# LogiGSM.net
KiCad netlist of a schematic drawn in EAGLE
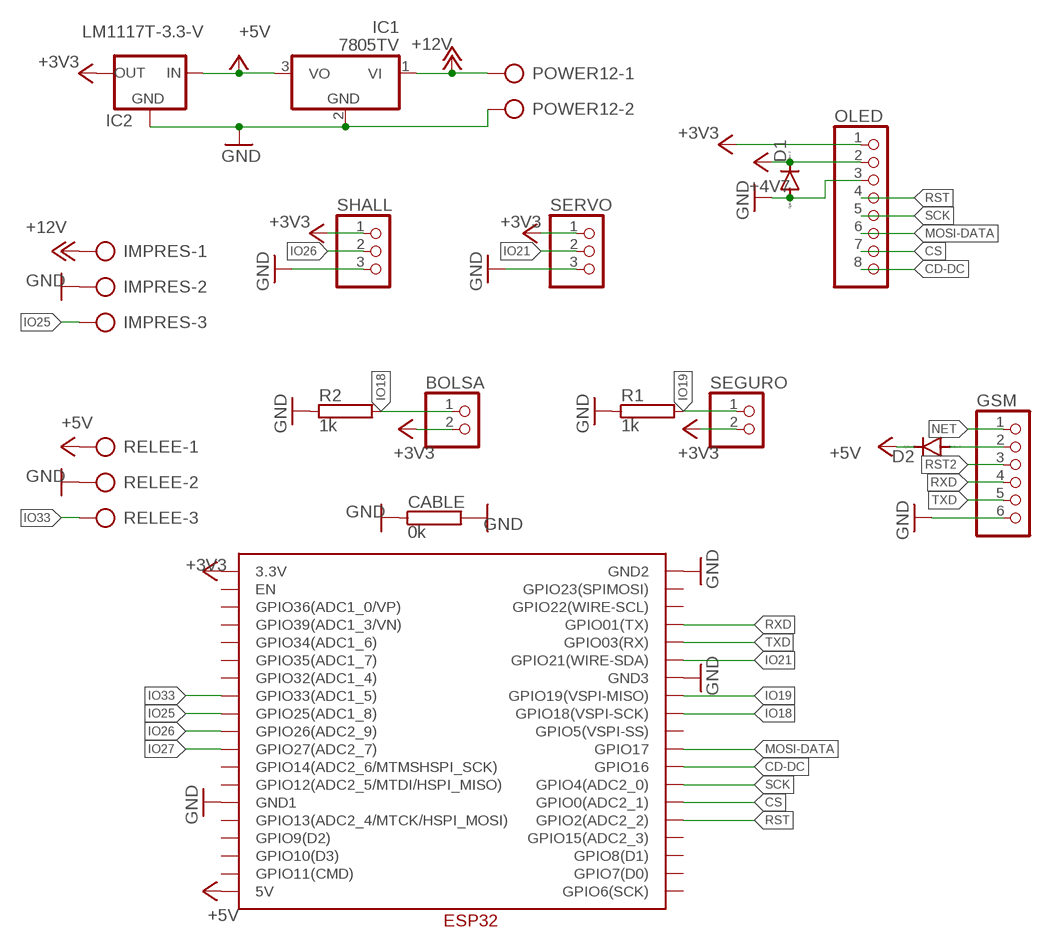
[diagram p0: schematic, sheet 1]

(export (version "E")
  (design (tool "Eeschema 10.0.6"))
  (components
    (comp (ref "BOLSA")
      (value "PINHD-1X2")
      (footprint "eagle-import:1X02")
      (libsource (lib "eagle-import") (part "PINHD-1X2"))
    )
    (comp (ref "CABLE")
      (value "0k")
      (footprint "eagle-import:RS1_2")
      (fields (field (name "MF") "OHMITE") (field (name "MPN") "RRS1K0E"))
      (libsource (lib "eagle-import") (part "RRS1/2"))
    )
    (comp (ref "D1")
      (value "DIODE-SOD81")
      (footprint "eagle-import:SOD81")
      (libsource (lib "eagle-import") (part "DIODE-SOD81"))
    )
    (comp (ref "D2")
      (value "DIODE-SOD81")
      (footprint "eagle-import:SOD81")
      (libsource (lib "eagle-import") (part "DIODE-SOD81"))
    )
    (comp (ref "GSM")
      (value "PINHD-1X6")
      (footprint "eagle-import:1X06")
      (libsource (lib "eagle-import") (part "PINHD-1X6"))
    )
    (comp (ref "IC1")
      (value "7805TV")
      (footprint "eagle-import:TO220V")
      (libsource (lib "eagle-import") (part "78TV05"))
    )
    (comp (ref "IC2")
      (value "LM1117T-3.3-V")
      (footprint "eagle-import:TO220V")
      (libsource (lib "eagle-import") (part "LM1117T--V3.3"))
    )
    (comp (ref "IMPRES")
      (value "AK500/3")
      (footprint "eagle-import:AK500_3")
      (libsource (lib "eagle-import") (part "AK500/3"))
    )
    (comp (ref "OLED")
      (value "PINHD-1X8")
      (footprint "eagle-import:1X08")
      (libsource (lib "eagle-import") (part "PINHD-1X8"))
    )
    (comp (ref "POWER12")
      (value "AK500/2")
      (footprint "eagle-import:AK500_2")
      (libsource (lib "eagle-import") (part "AK500/2"))
    )
    (comp (ref "R1")
      (value "1k")
      (footprint "eagle-import:RS1_8")
      (libsource (lib "eagle-import") (part "resistor-powerV2_RRS1/8"))
    )
    (comp (ref "R2")
      (value "1k")
      (footprint "eagle-import:RS1_8")
      (libsource (lib "eagle-import") (part "resistor-powerV2_RRS1/8"))
    )
    (comp (ref "RELEE")
      (value "AK500/3")
      (footprint "eagle-import:AK500_3")
      (libsource (lib "eagle-import") (part "AK500/3"))
    )
    (comp (ref "SEGURO")
      (value "PINHD-1X2")
      (footprint "eagle-import:1X02")
      (libsource (lib "eagle-import") (part "PINHD-1X2"))
    )
    (comp (ref "SERVO")
      (value "PINHD-1X3")
      (footprint "eagle-import:1X03")
      (libsource (lib "eagle-import") (part "PINHD-1X3"))
    )
    (comp (ref "SHALL")
      (value "PINHD-1X3")
      (footprint "eagle-import:1X03")
      (libsource (lib "eagle-import") (part "PINHD-1X3"))
    )
    (comp (ref "U$1")
      (value "ESP32WESP32W")
      (footprint "eagle-import:ESP32W")
      (libsource (lib "eagle-import") (part "ESP32WESP32W"))
    )
  )
  (nets
    (net (code "1") (name "+3V3") (class "Default")
      (node (ref "BOLSA") (pin "2") (pinfunction "2_2") (pintype "passive"))
      (node (ref "IC2") (pin "2") (pinfunction "OUT_2") (pintype "passive"))
      (node (ref "OLED") (pin "1") (pinfunction "1_1") (pintype "passive"))
      (node (ref "SEGURO") (pin "2") (pinfunction "2_2") (pintype "passive"))
      (node (ref "SERVO") (pin "1") (pinfunction "1_1") (pintype "passive"))
      (node (ref "SHALL") (pin "1") (pinfunction "1_1") (pintype "passive"))
      (node (ref "U$1") (pin "3.3V") (pinfunction "3.3V_3.3V") (pintype "bidirectional"))
    )
    (net (code "2") (name "+4V7") (class "Default")
      (node (ref "D1") (pin "C") (pinfunction "C_C") (pintype "passive"))
      (node (ref "D2") (pin "C") (pinfunction "C_C") (pintype "passive"))
      (node (ref "IC1") (pin "3") (pinfunction "VO_3") (pintype "passive"))
      (node (ref "IC2") (pin "3") (pinfunction "IN_3") (pintype "input"))
      (node (ref "OLED") (pin "2") (pinfunction "2_2") (pintype "passive"))
      (node (ref "RELEE") (pin "1") (pinfunction "KL_1") (pintype "passive"))
      (node (ref "U$1") (pin "5V") (pinfunction "5V_5V") (pintype "bidirectional"))
    )
    (net (code "3") (name "+12V") (class "Default")
      (node (ref "IC1") (pin "1") (pinfunction "VI_1") (pintype "input"))
      (node (ref "IMPRES") (pin "1") (pinfunction "KL_1") (pintype "passive"))
      (node (ref "POWER12") (pin "1") (pinfunction "KL_1") (pintype "passive"))
    )
    (net (code "4") (name "CD-DC") (class "Default")
      (node (ref "OLED") (pin "8") (pinfunction "8_8") (pintype "passive"))
      (node (ref "U$1") (pin "GPIO16") (pinfunction "GPIO16_GPIO16") (pintype "bidirectional"))
    )
    (net (code "5") (name "CS") (class "Default")
      (node (ref "OLED") (pin "7") (pinfunction "7_7") (pintype "passive"))
      (node (ref "U$1") (pin "GPIO0") (pinfunction "GPIO0(ADC2_1)_GPIO0") (pintype "bidirectional"))
    )
    (net (code "6") (name "GND") (class "Default")
      (node (ref "CABLE") (pin "1") (pinfunction "1_1") (pintype "passive"))
      (node (ref "CABLE") (pin "2") (pinfunction "2_2") (pintype "passive"))
      (node (ref "D1") (pin "A") (pinfunction "A_A") (pintype "passive"))
      (node (ref "GSM") (pin "6") (pinfunction "6_6") (pintype "passive"))
      (node (ref "IC1") (pin "2") (pinfunction "GND_2") (pintype "passive"))
      (node (ref "IC2") (pin "1") (pinfunction "GND_1") (pintype "input"))
      (node (ref "IMPRES") (pin "2") (pinfunction "KL_2") (pintype "passive"))
      (node (ref "OLED") (pin "3") (pinfunction "3_3") (pintype "passive"))
      (node (ref "POWER12") (pin "2") (pinfunction "KL_2") (pintype "passive"))
      (node (ref "R1") (pin "1") (pinfunction "1_1") (pintype "passive"))
      (node (ref "R2") (pin "1") (pinfunction "1_1") (pintype "passive"))
      (node (ref "RELEE") (pin "2") (pinfunction "KL_2") (pintype "passive"))
      (node (ref "SERVO") (pin "3") (pinfunction "3_3") (pintype "passive"))
      (node (ref "SHALL") (pin "3") (pinfunction "3_3") (pintype "passive"))
      (node (ref "U$1") (pin "GND1") (pinfunction "GND1_GND1") (pintype "bidirectional"))
      (node (ref "U$1") (pin "GND2") (pinfunction "GND2_GND2") (pintype "bidirectional"))
      (node (ref "U$1") (pin "GND3") (pinfunction "GND3_GND3") (pintype "bidirectional"))
    )
    (net (code "7") (name "IO18") (class "Default")
      (node (ref "BOLSA") (pin "1") (pinfunction "1_1") (pintype "passive"))
      (node (ref "R2") (pin "2") (pinfunction "2_2") (pintype "passive"))
      (node (ref "U$1") (pin "GPIO18") (pinfunction "GPIO18(VSPI-SCK)_GPIO18") (pintype "bidirectional"))
    )
    (net (code "8") (name "IO19") (class "Default")
      (node (ref "R1") (pin "2") (pinfunction "2_2") (pintype "passive"))
      (node (ref "SEGURO") (pin "1") (pinfunction "1_1") (pintype "passive"))
      (node (ref "U$1") (pin "GPIO19") (pinfunction "GPIO19(VSPI-MISO)_GPIO19") (pintype "bidirectional"))
    )
    (net (code "9") (name "IO21") (class "Default")
      (node (ref "SERVO") (pin "2") (pinfunction "2_2") (pintype "passive"))
      (node (ref "U$1") (pin "GPIO21") (pinfunction "GPIO21(WIRE-SDA)_GPIO21") (pintype "bidirectional"))
    )
    (net (code "10") (name "IO25") (class "Default")
      (node (ref "IMPRES") (pin "3") (pinfunction "KL_3") (pintype "passive"))
      (node (ref "U$1") (pin "GPIO25") (pinfunction "GPIO25(ADC1_8)_GPIO25") (pintype "bidirectional"))
    )
    (net (code "11") (name "IO26") (class "Default")
      (node (ref "SHALL") (pin "2") (pinfunction "2_2") (pintype "passive"))
      (node (ref "U$1") (pin "GPIO26") (pinfunction "GPIO26(ADC2_9)_GPIO26") (pintype "bidirectional"))
    )
    (net (code "12") (name "IO27") (class "Default")
      (node (ref "U$1") (pin "GPIO27") (pinfunction "GPIO27(ADC2_7)_GPIO27") (pintype "bidirectional"))
    )
    (net (code "13") (name "IO33") (class "Default")
      (node (ref "RELEE") (pin "3") (pinfunction "KL_3") (pintype "passive"))
      (node (ref "U$1") (pin "GPIO33") (pinfunction "GPIO33(ADC1_5)_GPIO33") (pintype "bidirectional"))
    )
    (net (code "14") (name "MOSI-DATA") (class "Default")
      (node (ref "OLED") (pin "6") (pinfunction "6_6") (pintype "passive"))
      (node (ref "U$1") (pin "GPIO17") (pinfunction "GPIO17_GPIO17") (pintype "bidirectional"))
    )
    (net (code "15") (name "NET") (class "Default")
      (node (ref "GSM") (pin "1") (pinfunction "1_1") (pintype "passive"))
    )
    (net (code "16") (name "Net-(D2-PadA)") (class "Default")
      (node (ref "D2") (pin "A") (pinfunction "A_A") (pintype "passive"))
      (node (ref "GSM") (pin "2") (pinfunction "2_2") (pintype "passive"))
    )
    (net (code "17") (name "RST") (class "Default")
      (node (ref "OLED") (pin "4") (pinfunction "4_4") (pintype "passive"))
      (node (ref "U$1") (pin "GPIO2") (pinfunction "GPIO2(ADC2_2)_GPIO2") (pintype "bidirectional"))
    )
    (net (code "18") (name "RST2") (class "Default")
      (node (ref "GSM") (pin "3") (pinfunction "3_3") (pintype "passive"))
    )
    (net (code "19") (name "RXD") (class "Default")
      (node (ref "GSM") (pin "4") (pinfunction "4_4") (pintype "passive"))
      (node (ref "U$1") (pin "TX") (pinfunction "GPIO01(TX)_TX") (pintype "bidirectional"))
    )
    (net (code "20") (name "SCK") (class "Default")
      (node (ref "OLED") (pin "5") (pinfunction "5_5") (pintype "passive"))
      (node (ref "U$1") (pin "GPIO4") (pinfunction "GPIO4(ADC2_0)_GPIO4") (pintype "bidirectional"))
    )
    (net (code "21") (name "TXD") (class "Default")
      (node (ref "GSM") (pin "5") (pinfunction "5_5") (pintype "passive"))
      (node (ref "U$1") (pin "RX") (pinfunction "GPIO03(RX)_RX") (pintype "bidirectional"))
    )
    (net (code "22") (name "unconnected-(U$1-GPIO5(VSPI-SS)-PadGPIO5)") (class "Default")
      (node (ref "U$1") (pin "GPIO5") (pinfunction "GPIO5(VSPI-SS)_GPIO5") (pintype "bidirectional"))
    )
    (net (code "23") (name "unconnected-(U$1-GPIO6(SCK)-PadCLK)") (class "Default")
      (node (ref "U$1") (pin "CLK") (pinfunction "GPIO6(SCK)_CLK") (pintype "bidirectional"))
    )
    (net (code "24") (name "unconnected-(U$1-GPIO7(D0)-PadSDO)") (class "Default")
      (node (ref "U$1") (pin "SDO") (pinfunction "GPIO7(D0)_SDO") (pintype "bidirectional"))
    )
    (net (code "25") (name "unconnected-(U$1-GPIO8(D1)-PadSDI)") (class "Default")
      (node (ref "U$1") (pin "SDI") (pinfunction "GPIO8(D1)_SDI") (pintype "bidirectional"))
    )
    (net (code "26") (name "unconnected-(U$1-GPIO9(D2)-PadD2)") (class "Default")
      (node (ref "U$1") (pin "D2") (pinfunction "GPIO9(D2)_D2") (pintype "bidirectional"))
    )
    (net (code "27") (name "unconnected-(U$1-GPIO10(D3)-PadD3)") (class "Default")
      (node (ref "U$1") (pin "D3") (pinfunction "GPIO10(D3)_D3") (pintype "bidirectional"))
    )
    (net (code "28") (name "unconnected-(U$1-GPIO11(CMD)-PadCMD)") (class "Default")
      (node (ref "U$1") (pin "CMD") (pinfunction "GPIO11(CMD)_CMD") (pintype "bidirectional"))
    )
    (net (code "29") (name "unconnected-(U$1-GPIO12(ADC2_5{slash}MTDI{slash}HSPI_MISO)-PadGPIO12)") (class "Default")
      (node (ref "U$1") (pin "GPIO12") (pinfunction "GPIO12(ADC2_5/MTDI/HSPI_MISO)_GPIO12") (pintype "bidirectional"))
    )
    (net (code "30") (name "unconnected-(U$1-GPIO13(ADC2_4{slash}MTCK{slash}HSPI_MOSI)-PadGPIO13)") (class "Default")
      (node (ref "U$1") (pin "GPIO13") (pinfunction "GPIO13(ADC2_4/MTCK/HSPI_MOSI)_GPIO13") (pintype "bidirectional"))
    )
    (net (code "31") (name "unconnected-(U$1-GPIO14(ADC2_6{slash}MTMSHSPI_SCK)-PadGPIO14)") (class "Default")
      (node (ref "U$1") (pin "GPIO14") (pinfunction "GPIO14(ADC2_6/MTMSHSPI_SCK)_GPIO14") (pintype "bidirectional"))
    )
    (net (code "32") (name "unconnected-(U$1-GPIO15(ADC2_3)-PadGPIO15)") (class "Default")
      (node (ref "U$1") (pin "GPIO15") (pinfunction "GPIO15(ADC2_3)_GPIO15") (pintype "bidirectional"))
    )
    (net (code "33") (name "unconnected-(U$1-GPIO22(WIRE-SCL)-PadGPIO22)") (class "Default")
      (node (ref "U$1") (pin "GPIO22") (pinfunction "GPIO22(WIRE-SCL)_GPIO22") (pintype "bidirectional"))
    )
    (net (code "34") (name "unconnected-(U$1-GPIO23(SPIMOSI)-PadGPIO23)") (class "Default")
      (node (ref "U$1") (pin "GPIO23") (pinfunction "GPIO23(SPIMOSI)_GPIO23") (pintype "bidirectional"))
    )
    (net (code "35") (name "unconnected-(U$1-GPIO32(ADC1_4)-PadGPIO32)") (class "Default")
      (node (ref "U$1") (pin "GPIO32") (pinfunction "GPIO32(ADC1_4)_GPIO32") (pintype "bidirectional"))
    )
    (net (code "36") (name "unconnected-(U$1-GPIO34(ADC1_6)-PadGPIO34)") (class "Default")
      (node (ref "U$1") (pin "GPIO34") (pinfunction "GPIO34(ADC1_6)_GPIO34") (pintype "bidirectional"))
    )
    (net (code "37") (name "unconnected-(U$1-GPIO35(ADC1_7)-PadGPIO35)") (class "Default")
      (node (ref "U$1") (pin "GPIO35") (pinfunction "GPIO35(ADC1_7)_GPIO35") (pintype "bidirectional"))
    )
    (net (code "38") (name "unconnected-(U$1-GPIO36(ADC1_0{slash}VP)-PadVP)") (class "Default")
      (node (ref "U$1") (pin "VP") (pinfunction "GPIO36(ADC1_0/VP)_VP") (pintype "bidirectional"))
    )
    (net (code "39") (name "unconnected-(U$1-GPIO39(ADC1_3{slash}VN)-PadVN)") (class "Default")
      (node (ref "U$1") (pin "VN") (pinfunction "GPIO39(ADC1_3/VN)_VN") (pintype "bidirectional"))
    )
    (net (code "40") (name "unconnected-(U$1-PadEN)") (class "Default")
      (node (ref "U$1") (pin "EN") (pinfunction "EN_EN") (pintype "bidirectional"))
    )
  )
)
